# CAN_Cape_v2_1.net
KiCad netlist of a schematic drawn in EAGLE
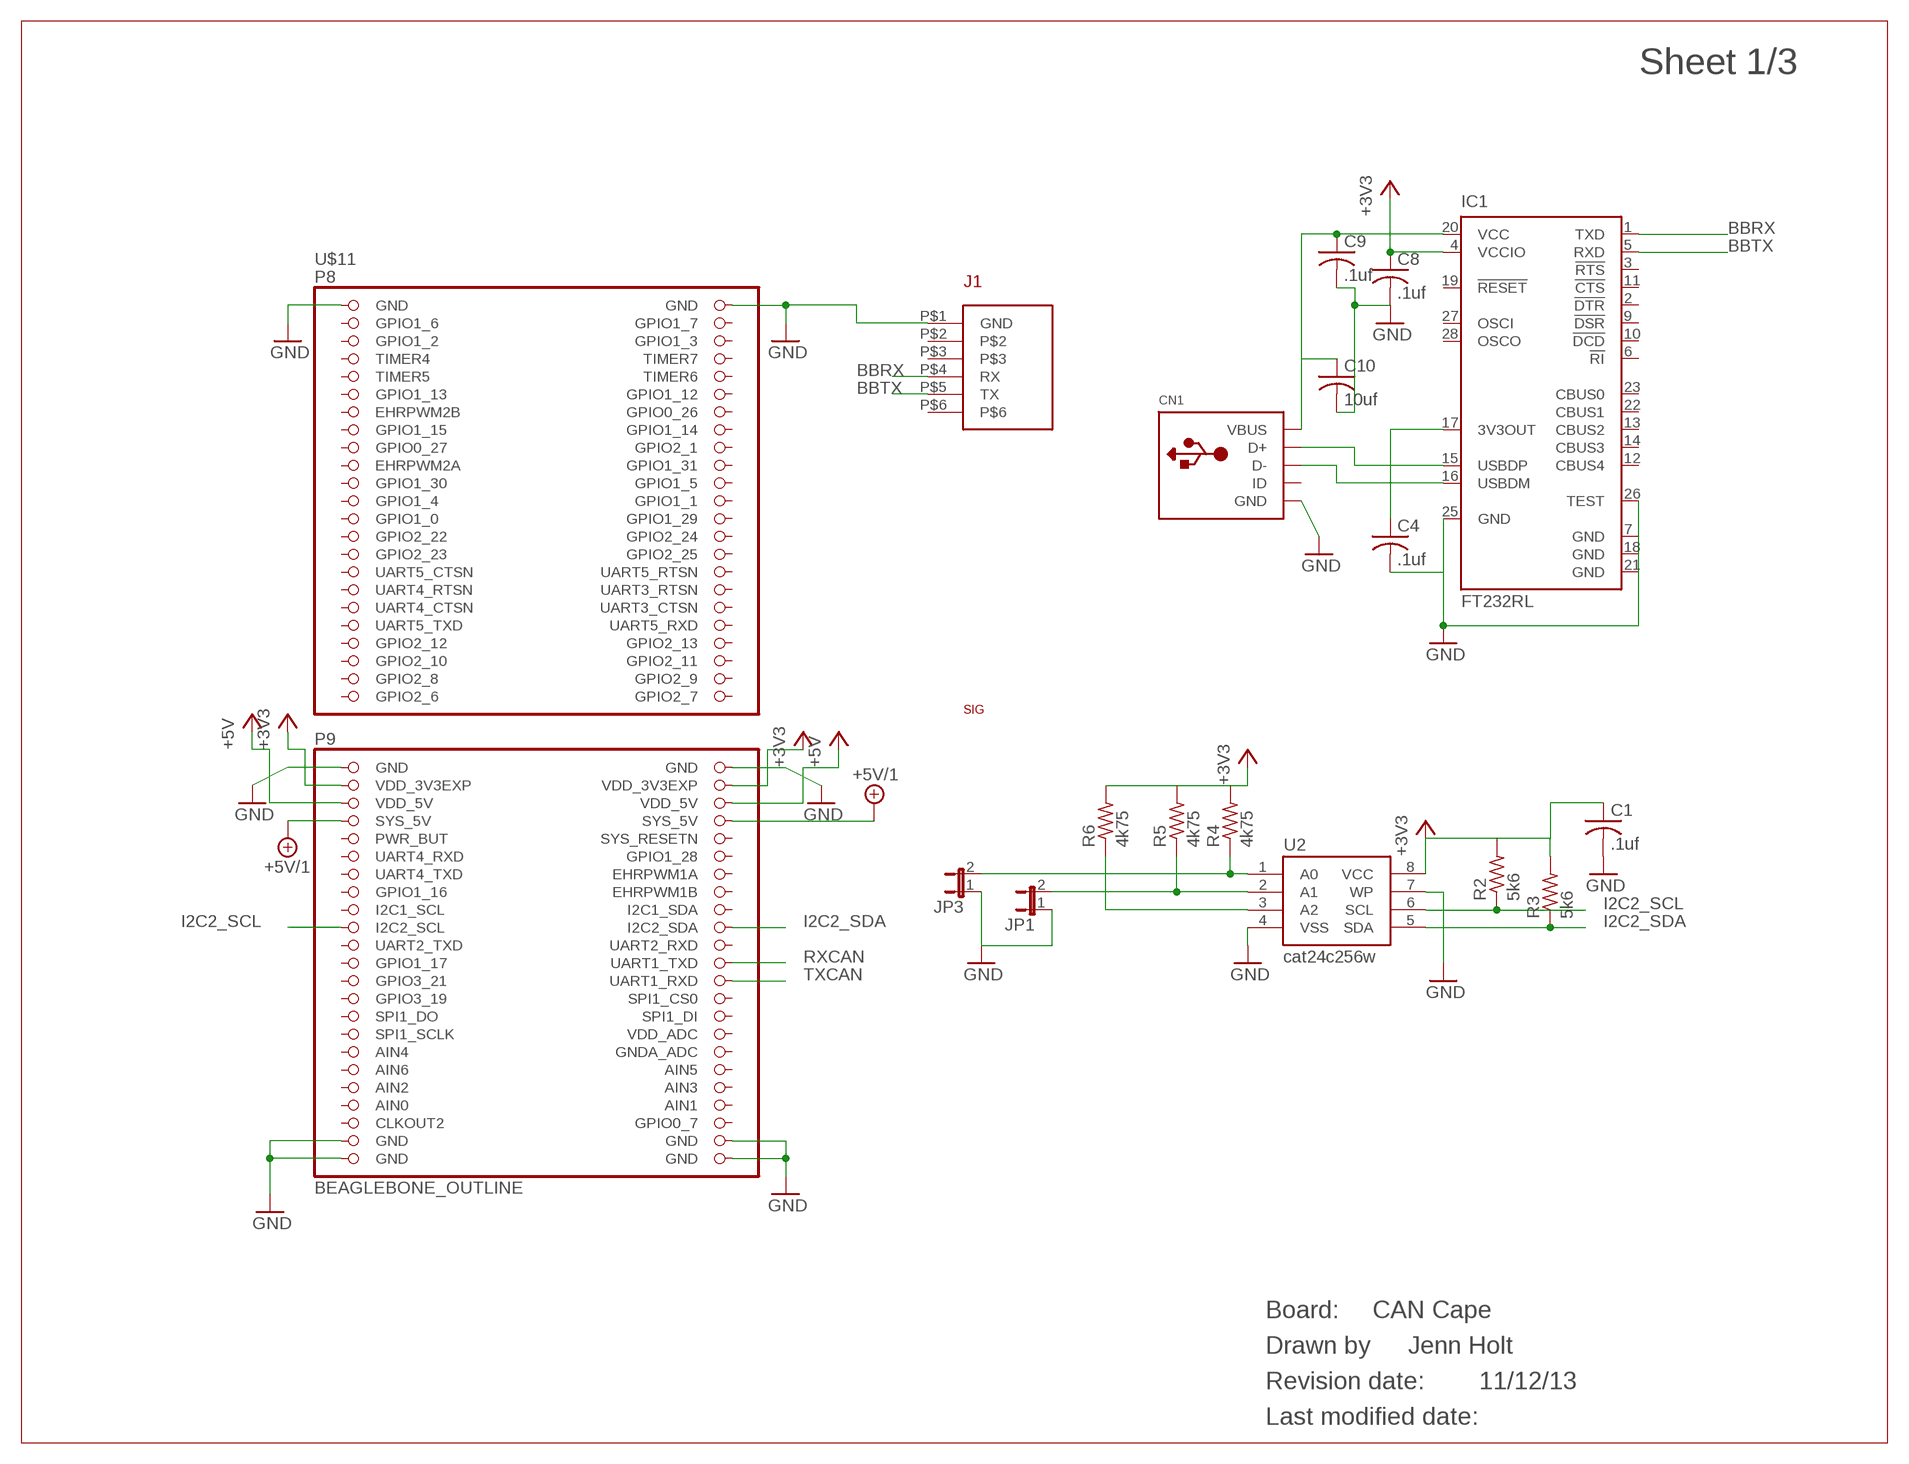
[diagram p0: schematic, sheet 1]
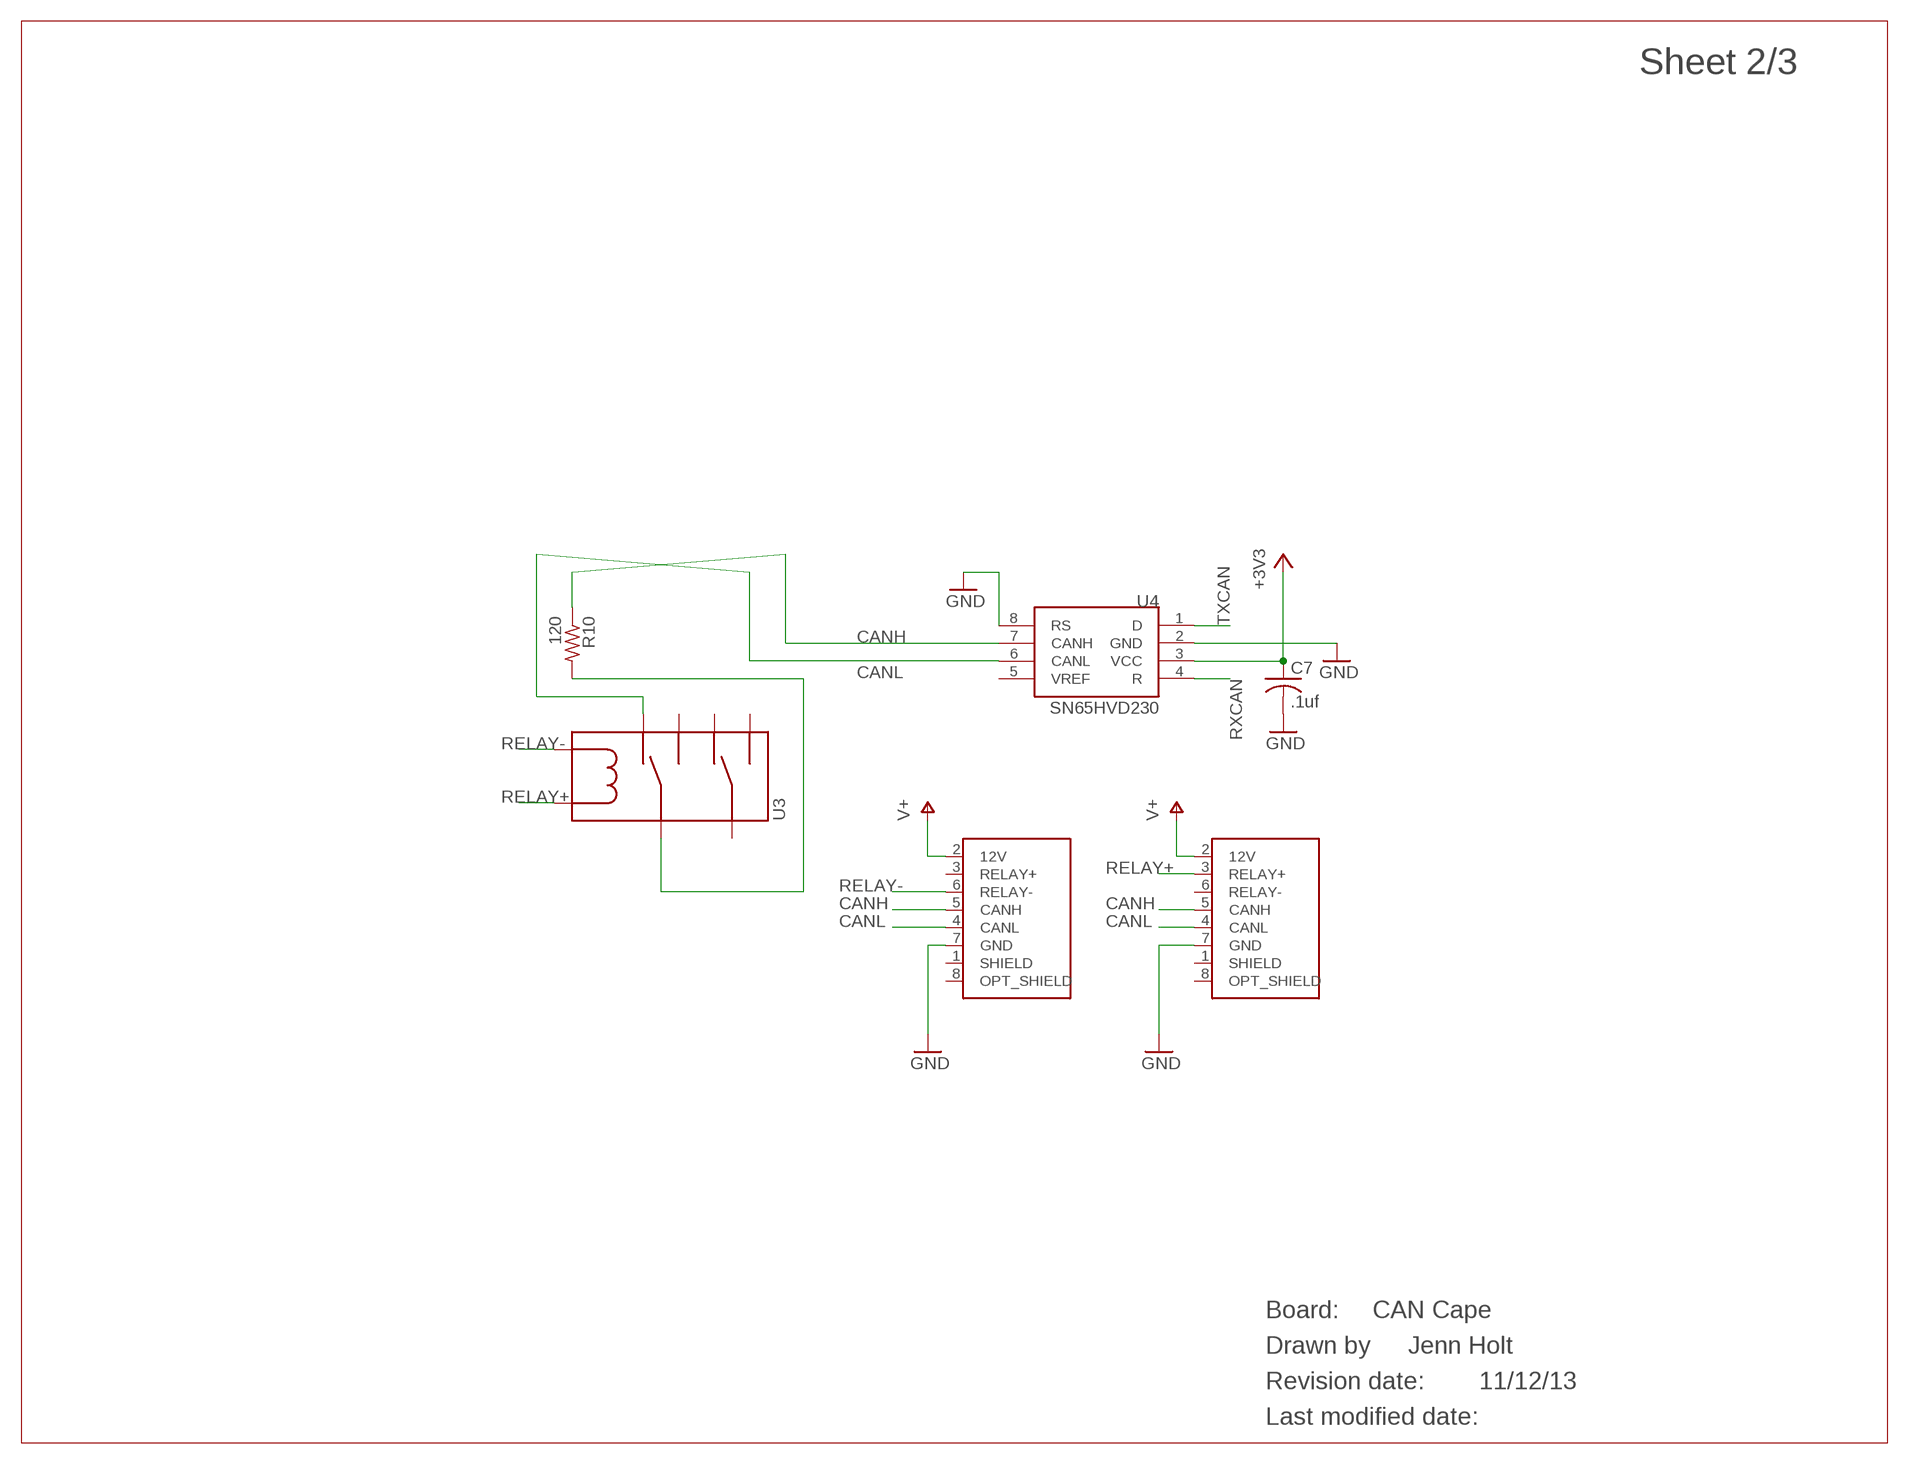
[diagram p1: schematic, sheet 2]
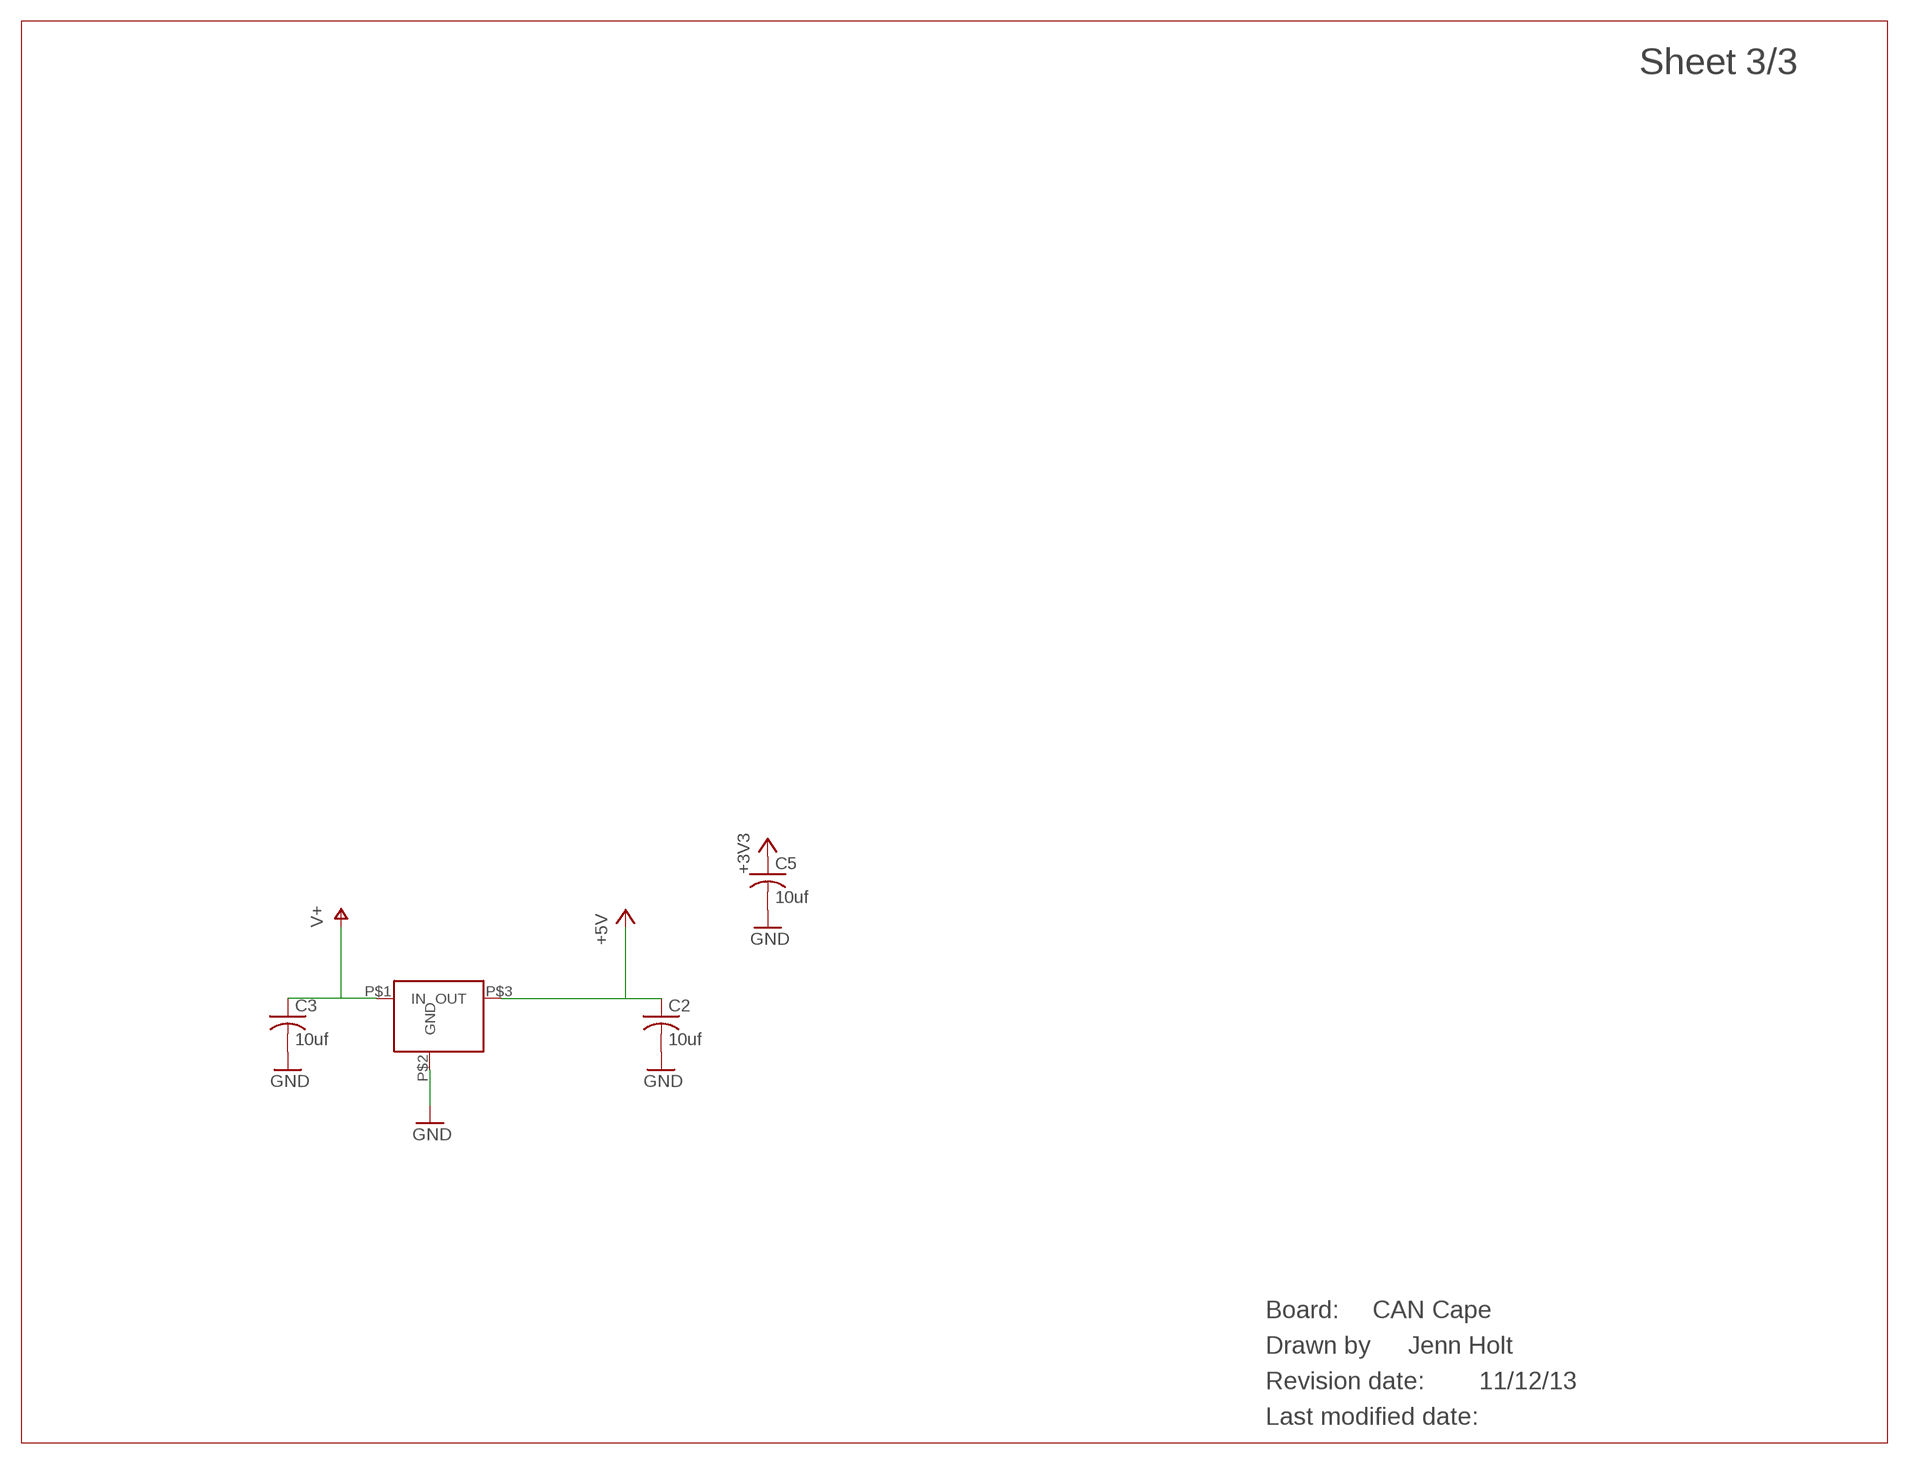
[diagram p2: schematic, sheet 3]

(export (version "E")
  (design (tool "Eeschema 10.0.6"))
  (components
    (comp (ref "C2")
      (value "10uf")
      (footprint "eagle-import:C0805")
      (fields (field (name "PARTNO") "GRM21BR61C106KE15L"))
      (libsource (lib "eagle-import") (part "C-USC0805"))
    )
    (comp (ref "C3")
      (value "10uf")
      (footprint "eagle-import:C0805")
      (fields (field (name "PARTNO") "GRM21BR61C106KE15L"))
      (libsource (lib "eagle-import") (part "C-USC0805"))
    )
    (comp (ref "C5")
      (value "10uf")
      (footprint "eagle-import:C0805")
      (fields (field (name "PARTNO") "GRM21BR61C106KE15L"))
      (libsource (lib "eagle-import") (part "C-USC0805"))
    )
    (comp (ref "U$4")
      (value "CURRENT-C-LETTER-LANDSCAPE")
      (footprint "eagle-import:BLANK")
      (libsource (lib "eagle-import") (part "CURRENT-C-LETTER-LANDSCAPE"))
    )
    (comp (ref "U1")
      (value "RECOM_DCDC")
      (footprint "eagle-import:INNOLINE-SIP")
      (fields (field (name "PARTNO") "R-78C5.0-1.0"))
      (libsource (lib "eagle-import") (part "RECOM_DCDC"))
    )
    (comp (ref "C7")
      (value ".1uf")
      (footprint "eagle-import:C0603")
      (fields (field (name "PARTNO") "C1608X7R1E104K080AA"))
      (libsource (lib "eagle-import") (part "C-USC0603"))
    )
    (comp (ref "R10")
      (value "120")
      (footprint "eagle-import:R0603")
      (fields (field (name "PARTNO") "RC0805FR-07120RL"))
      (libsource (lib "eagle-import") (part "R-US_R0603"))
    )
    (comp (ref "U$6")
      (value "CANBUS2VERT")
      (footprint "eagle-import:776276-1_AMPSEAL_8_VERT")
      (fields (field (name "PARTNO") "1-776276-1"))
      (libsource (lib "eagle-import") (part "CANBUS2VERT"))
    )
    (comp (ref "U$7")
      (value "CANBUS2VERT")
      (footprint "eagle-import:776276-1_AMPSEAL_8_VERT")
      (fields (field (name "PARTNO") "1-776276-1"))
      (libsource (lib "eagle-import") (part "CANBUS2VERT"))
    )
    (comp (ref "U$9")
      (value "CURRENT-C-LETTER-LANDSCAPE")
      (footprint "eagle-import:BLANK")
      (libsource (lib "eagle-import") (part "CURRENT-C-LETTER-LANDSCAPE"))
    )
    (comp (ref "U3")
      (value "IM_RELAY")
      (footprint "eagle-import:IM_RELAY")
      (fields (field (name "PARTNO") "IM26GR"))
      (libsource (lib "eagle-import") (part "IM_RELAY"))
    )
    (comp (ref "U4")
      (value "SN65HVD230")
      (footprint "eagle-import:SOIC8")
      (fields (field (name "PARTNO") "SN65HVD230D"))
      (libsource (lib "eagle-import") (part "SN65HVD230"))
    )
    (comp (ref "C1")
      (value ".1uf")
      (footprint "eagle-import:C0603")
      (fields (field (name "PARTNO") "C1608X7R1E104K080AA"))
      (libsource (lib "eagle-import") (part "C-USC0603"))
    )
    (comp (ref "C4")
      (value ".1uf")
      (footprint "eagle-import:C0603")
      (fields (field (name "PARTNO") "C1608X7R1E104K080AA"))
      (libsource (lib "eagle-import") (part "C-USC0603"))
    )
    (comp (ref "C8")
      (value ".1uf")
      (footprint "eagle-import:C0603")
      (fields (field (name "PARTNO") "C1608X7R1E104K080AA"))
      (libsource (lib "eagle-import") (part "C-USC0603"))
    )
    (comp (ref "C9")
      (value ".1uf")
      (footprint "eagle-import:C0603")
      (fields (field (name "PARTNO") "C1608X7R1E104K080AA"))
      (libsource (lib "eagle-import") (part "C-USC0603"))
    )
    (comp (ref "C10")
      (value "10uf")
      (footprint "eagle-import:C0805")
      (fields (field (name "PARTNO") "GRM21BR61C106KE15L"))
      (libsource (lib "eagle-import") (part "C-USC0805"))
    )
    (comp (ref "CN1")
      (value "USBMINIB")
      (footprint "eagle-import:USB-MINIB")
      (fields (field (name "PARTNO") "1734035-2"))
      (libsource (lib "eagle-import") (part "USBMINIB"))
    )
    (comp (ref "IC1")
      (value "FT232RL")
      (footprint "eagle-import:SSOP28")
      (libsource (lib "eagle-import") (part "FT232RL"))
    )
    (comp (ref "JP1")
      (value "JUMPER-2SMD-NO")
      (footprint "eagle-import:SJ_2S-NO")
      (libsource (lib "eagle-import") (part "JUMPER-2SMD-NO"))
    )
    (comp (ref "JP3")
      (value "JUMPER-2SMD-NO")
      (footprint "eagle-import:SJ_2S-NO")
      (libsource (lib "eagle-import") (part "JUMPER-2SMD-NO"))
    )
    (comp (ref "R2")
      (value "5k6")
      (footprint "eagle-import:R0603")
      (fields (field (name "PARTNO") "ERJ-3EKF4701V"))
      (libsource (lib "eagle-import") (part "R-US_R0603"))
    )
    (comp (ref "R3")
      (value "5k6")
      (footprint "eagle-import:R0603")
      (fields (field (name "PARTNO") "ERJ-3EKF4701V"))
      (libsource (lib "eagle-import") (part "R-US_R0603"))
    )
    (comp (ref "R4")
      (value "4k75")
      (footprint "eagle-import:R0603")
      (fields (field (name "PARTNO") "ERJ-3EKF4701V"))
      (libsource (lib "eagle-import") (part "R-US_R0603"))
    )
    (comp (ref "R5")
      (value "4k75")
      (footprint "eagle-import:R0603")
      (fields (field (name "PARTNO") "ERJ-3EKF4701V"))
      (libsource (lib "eagle-import") (part "R-US_R0603"))
    )
    (comp (ref "R6")
      (value "4k75")
      (footprint "eagle-import:R0603")
      (fields (field (name "PARTNO") "ERJ-3EKF4701V"))
      (libsource (lib "eagle-import") (part "R-US_R0603"))
    )
    (comp (ref "U$5")
      (value "SIG")
      (footprint "eagle-import:SIG")
      (libsource (lib "eagle-import") (part "SIG"))
    )
    (comp (ref "U$10")
      (value "CURRENT-C-LETTER-LANDSCAPE")
      (footprint "eagle-import:BLANK")
      (libsource (lib "eagle-import") (part "CURRENT-C-LETTER-LANDSCAPE"))
    )
    (comp (ref "U$11")
      (value "BEAGLEBONE_OUTLINE")
      (footprint "eagle-import:BEAGLEBONE_SHIELD")
      (libsource (lib "eagle-import") (part "BEAGLEBONE_OUTLINE"))
    )
    (comp (ref "U2")
      (value "cat24c256w")
      (footprint "eagle-import:SO08")
      (fields (field (name "PARTNO") "CAT24C256WI-GT3"))
      (libsource (lib "eagle-import") (part "EEPROM-I2CSMD"))
    )
  )
  (nets
    (net (code "1") (name "+3V3") (class "Default")
      (node (ref "C1") (pin "1") (pinfunction "1_1") (pintype "passive"))
      (node (ref "C5") (pin "1") (pinfunction "1_1") (pintype "passive"))
      (node (ref "C7") (pin "1") (pinfunction "1_1") (pintype "passive"))
      (node (ref "C8") (pin "1") (pinfunction "1_1") (pintype "passive"))
      (node (ref "IC1") (pin "4") (pinfunction "VCCIO_4") (pintype "power_in"))
      (node (ref "R2") (pin "2") (pinfunction "2_2") (pintype "passive"))
      (node (ref "R3") (pin "2") (pinfunction "2_2") (pintype "passive"))
      (node (ref "R4") (pin "2") (pinfunction "2_2") (pintype "passive"))
      (node (ref "R5") (pin "2") (pinfunction "2_2") (pintype "passive"))
      (node (ref "R6") (pin "2") (pinfunction "2_2") (pintype "passive"))
      (node (ref "U$11") (pin "49") (pinfunction "VDD_3V3EXP_49") (pintype "power_in"))
      (node (ref "U$11") (pin "50") (pinfunction "VDD_3V3EXP_50") (pintype "power_in"))
      (node (ref "U2") (pin "8") (pinfunction "VCC_8") (pintype "power_in"))
      (node (ref "U4") (pin "3") (pinfunction "VCC_3") (pintype "bidirectional"))
    )
    (net (code "2") (name "+5V") (class "Default")
      (node (ref "C2") (pin "1") (pinfunction "1_1") (pintype "passive"))
      (node (ref "U$11") (pin "51") (pinfunction "VDD_5V_51") (pintype "power_in"))
      (node (ref "U$11") (pin "52") (pinfunction "VDD_5V_52") (pintype "power_in"))
      (node (ref "U1") (pin "P$3") (pinfunction "OUT_P$3") (pintype "bidirectional"))
    )
    (net (code "3") (name "+5V{slash}1") (class "Default")
      (node (ref "U$11") (pin "53") (pinfunction "SYS_5V_53") (pintype "power_in"))
      (node (ref "U$11") (pin "54") (pinfunction "SYS_5V_54") (pintype "passive"))
    )
    (net (code "4") (name "AIN0") (class "Default")
      (node (ref "U$11") (pin "85") (pinfunction "AIN0_85") (pintype "power_in"))
    )
    (net (code "5") (name "BBRX") (class "Default")
      (node (ref "IC1") (pin "1") (pinfunction "TXD_1") (pintype "output"))
      (node (ref "U$11") (pin "P$4") (pinfunction "RX_P$4") (pintype "bidirectional"))
    )
    (net (code "6") (name "BBTX") (class "Default")
      (node (ref "IC1") (pin "5") (pinfunction "RXD_5") (pintype "input"))
      (node (ref "U$11") (pin "P$5") (pinfunction "TX_P$5") (pintype "bidirectional"))
    )
    (net (code "7") (name "CANH") (class "Default")
      (node (ref "R10") (pin "1") (pinfunction "1_1") (pintype "passive"))
      (node (ref "U$6") (pin "5") (pinfunction "CANH_5") (pintype "bidirectional"))
      (node (ref "U$7") (pin "5") (pinfunction "CANH_5") (pintype "bidirectional"))
      (node (ref "U4") (pin "7") (pinfunction "CANH_7") (pintype "bidirectional"))
    )
    (net (code "8") (name "CANL") (class "Default")
      (node (ref "U$6") (pin "4") (pinfunction "CANL_4") (pintype "bidirectional"))
      (node (ref "U$7") (pin "4") (pinfunction "CANL_4") (pintype "bidirectional"))
      (node (ref "U3") (pin "2") (pinfunction "NC1_2") (pintype "passive"))
      (node (ref "U4") (pin "6") (pinfunction "CANL_6") (pintype "bidirectional"))
    )
    (net (code "9") (name "GND") (class "Default")
      (node (ref "C1") (pin "2") (pinfunction "2_2") (pintype "passive"))
      (node (ref "C10") (pin "2") (pinfunction "2_2") (pintype "passive"))
      (node (ref "C2") (pin "2") (pinfunction "2_2") (pintype "passive"))
      (node (ref "C3") (pin "2") (pinfunction "2_2") (pintype "passive"))
      (node (ref "C4") (pin "2") (pinfunction "2_2") (pintype "passive"))
      (node (ref "C5") (pin "2") (pinfunction "2_2") (pintype "passive"))
      (node (ref "C7") (pin "2") (pinfunction "2_2") (pintype "passive"))
      (node (ref "C8") (pin "2") (pinfunction "2_2") (pintype "passive"))
      (node (ref "C9") (pin "2") (pinfunction "2_2") (pintype "passive"))
      (node (ref "CN1") (pin "GND") (pinfunction "GND_GND") (pintype "power_in"))
      (node (ref "IC1") (pin "18") (pinfunction "GND_18") (pintype "power_in"))
      (node (ref "IC1") (pin "21") (pinfunction "GND_21") (pintype "power_in"))
      (node (ref "IC1") (pin "25") (pinfunction "GND_25") (pintype "power_in"))
      (node (ref "IC1") (pin "26") (pinfunction "TEST_26") (pintype "input"))
      (node (ref "IC1") (pin "7") (pinfunction "GND_7") (pintype "power_in"))
      (node (ref "JP1") (pin "1") (pinfunction "1_1") (pintype "passive"))
      (node (ref "JP3") (pin "1") (pinfunction "1_1") (pintype "passive"))
      (node (ref "U$11") (pin "1") (pinfunction "GND_1") (pintype "power_in"))
      (node (ref "U$11") (pin "2") (pinfunction "GND_2") (pintype "power_in"))
      (node (ref "U$11") (pin "47") (pinfunction "GND_47") (pintype "power_in"))
      (node (ref "U$11") (pin "48") (pinfunction "GND_48") (pintype "power_in"))
      (node (ref "U$11") (pin "89") (pinfunction "GND_89") (pintype "power_in"))
      (node (ref "U$11") (pin "90") (pinfunction "GND_90") (pintype "power_in"))
      (node (ref "U$11") (pin "91") (pinfunction "GND_91") (pintype "power_in"))
      (node (ref "U$11") (pin "92") (pinfunction "GND_92") (pintype "power_in"))
      (node (ref "U$11") (pin "P$1") (pinfunction "GND_P$1") (pintype "bidirectional"))
      (node (ref "U$6") (pin "7") (pinfunction "GND_7") (pintype "bidirectional"))
      (node (ref "U$7") (pin "7") (pinfunction "GND_7") (pintype "bidirectional"))
      (node (ref "U1") (pin "P$2") (pinfunction "GND_P$2") (pintype "bidirectional"))
      (node (ref "U2") (pin "4") (pinfunction "VSS_4") (pintype "power_in"))
      (node (ref "U2") (pin "7") (pinfunction "WP_7") (pintype "bidirectional"))
      (node (ref "U4") (pin "2") (pinfunction "GND_2") (pintype "bidirectional"))
      (node (ref "U4") (pin "8") (pinfunction "RS_8") (pintype "bidirectional"))
    )
    (net (code "10") (name "I2C2_SCL") (class "Default")
      (node (ref "R2") (pin "1") (pinfunction "1_1") (pintype "passive"))
      (node (ref "U$11") (pin "65") (pinfunction "I2C2_SCL_65") (pintype "passive"))
      (node (ref "U2") (pin "6") (pinfunction "SCL_6") (pintype "bidirectional"))
    )
    (net (code "11") (name "I2C2_SDA") (class "Default")
      (node (ref "R3") (pin "1") (pinfunction "1_1") (pintype "passive"))
      (node (ref "U$11") (pin "66") (pinfunction "I2C2_SDA_66") (pintype "passive"))
      (node (ref "U2") (pin "5") (pinfunction "SDA_5") (pintype "bidirectional"))
    )
    (net (code "12") (name "Net-(IC1-3V3OUT)") (class "Default")
      (node (ref "C4") (pin "1") (pinfunction "1_1") (pintype "passive"))
      (node (ref "IC1") (pin "17") (pinfunction "3V3OUT_17") (pintype "output"))
    )
    (net (code "13") (name "Net-(IC1-USBDM)") (class "Default")
      (node (ref "CN1") (pin "D-") (pinfunction "D-_D-") (pintype "bidirectional"))
      (node (ref "IC1") (pin "16") (pinfunction "USBDM_16") (pintype "bidirectional"))
    )
    (net (code "14") (name "Net-(IC1-USBDP)") (class "Default")
      (node (ref "CN1") (pin "D+") (pinfunction "D+_D+") (pintype "bidirectional"))
      (node (ref "IC1") (pin "15") (pinfunction "USBDP_15") (pintype "bidirectional"))
    )
    (net (code "15") (name "Net-(IC1-VCC)") (class "Default")
      (node (ref "C10") (pin "1") (pinfunction "1_1") (pintype "passive"))
      (node (ref "C9") (pin "1") (pinfunction "1_1") (pintype "passive"))
      (node (ref "CN1") (pin "VBUS") (pinfunction "VBUS_VBUS") (pintype "power_in"))
      (node (ref "IC1") (pin "20") (pinfunction "VCC_20") (pintype "power_in"))
    )
    (net (code "16") (name "Net-(U2-A0)") (class "Default")
      (node (ref "JP3") (pin "2") (pinfunction "2_2") (pintype "passive"))
      (node (ref "R4") (pin "1") (pinfunction "1_1") (pintype "passive"))
      (node (ref "U2") (pin "1") (pinfunction "A0_1") (pintype "bidirectional"))
    )
    (net (code "17") (name "Net-(U2-A1)") (class "Default")
      (node (ref "JP1") (pin "2") (pinfunction "2_2") (pintype "passive"))
      (node (ref "R5") (pin "1") (pinfunction "1_1") (pintype "passive"))
      (node (ref "U2") (pin "2") (pinfunction "A1_2") (pintype "bidirectional"))
    )
    (net (code "18") (name "Net-(U2-A2)") (class "Default")
      (node (ref "R6") (pin "1") (pinfunction "1_1") (pintype "passive"))
      (node (ref "U2") (pin "3") (pinfunction "A2_3") (pintype "bidirectional"))
    )
    (net (code "19") (name "Net-(U3-COM1)") (class "Default")
      (node (ref "R10") (pin "2") (pinfunction "2_2") (pintype "passive"))
      (node (ref "U3") (pin "3") (pinfunction "COM1_3") (pintype "passive"))
    )
    (net (code "20") (name "RELAY+") (class "Default")
      (node (ref "U$7") (pin "3") (pinfunction "RELAY+_3") (pintype "bidirectional"))
      (node (ref "U3") (pin "1") (pinfunction "C1_1") (pintype "passive"))
    )
    (net (code "21") (name "RELAY-") (class "Default")
      (node (ref "U$6") (pin "6") (pinfunction "RELAY-_6") (pintype "bidirectional"))
      (node (ref "U3") (pin "8") (pinfunction "C2_8") (pintype "passive"))
    )
    (net (code "22") (name "RXCAN") (class "Default")
      (node (ref "U$11") (pin "70") (pinfunction "UART1_TXD_70") (pintype "passive"))
      (node (ref "U4") (pin "4") (pinfunction "R_4") (pintype "bidirectional"))
    )
    (net (code "23") (name "TXCAN") (class "Default")
      (node (ref "U$11") (pin "72") (pinfunction "UART1_RXD_72") (pintype "passive"))
      (node (ref "U4") (pin "1") (pinfunction "D_1") (pintype "bidirectional"))
    )
    (net (code "24") (name "V+") (class "Default")
      (node (ref "C3") (pin "1") (pinfunction "1_1") (pintype "passive"))
      (node (ref "U$6") (pin "2") (pinfunction "12V_2") (pintype "bidirectional"))
      (node (ref "U$7") (pin "2") (pinfunction "12V_2") (pintype "bidirectional"))
      (node (ref "U1") (pin "P$1") (pinfunction "IN_P$1") (pintype "bidirectional"))
    )
    (net (code "25") (name "unconnected-(CN1-PadID)") (class "Default")
      (node (ref "CN1") (pin "ID") (pinfunction "ID_ID") (pintype "bidirectional"))
    )
    (net (code "26") (name "unconnected-(IC1-CBUS0-Pad23)") (class "Default")
      (node (ref "IC1") (pin "23") (pinfunction "CBUS0_23") (pintype "bidirectional"))
    )
    (net (code "27") (name "unconnected-(IC1-CBUS1-Pad22)") (class "Default")
      (node (ref "IC1") (pin "22") (pinfunction "CBUS1_22") (pintype "bidirectional"))
    )
    (net (code "28") (name "unconnected-(IC1-CBUS2-Pad13)") (class "Default")
      (node (ref "IC1") (pin "13") (pinfunction "CBUS2_13") (pintype "bidirectional"))
    )
    (net (code "29") (name "unconnected-(IC1-CBUS3-Pad14)") (class "Default")
      (node (ref "IC1") (pin "14") (pinfunction "CBUS3_14") (pintype "bidirectional"))
    )
    (net (code "30") (name "unconnected-(IC1-CBUS4-Pad12)") (class "Default")
      (node (ref "IC1") (pin "12") (pinfunction "CBUS4_12") (pintype "bidirectional"))
    )
    (net (code "31") (name "unconnected-(IC1-OSCI-Pad27)") (class "Default")
      (node (ref "IC1") (pin "27") (pinfunction "OSCI_27") (pintype "input"))
    )
    (net (code "32") (name "unconnected-(IC1-OSCO-Pad28)") (class "Default")
      (node (ref "IC1") (pin "28") (pinfunction "OSCO_28") (pintype "output"))
    )
    (net (code "33") (name "unconnected-(IC1-~{CTS}-Pad11)") (class "Default")
      (node (ref "IC1") (pin "11") (pinfunction "~{CTS}_11") (pintype "input"))
    )
    (net (code "34") (name "unconnected-(IC1-~{DCD}-Pad10)") (class "Default")
      (node (ref "IC1") (pin "10") (pinfunction "~{DCD}_10") (pintype "input"))
    )
    (net (code "35") (name "unconnected-(IC1-~{DSR}-Pad9)") (class "Default")
      (node (ref "IC1") (pin "9") (pinfunction "~{DSR}_9") (pintype "input"))
    )
    (net (code "36") (name "unconnected-(IC1-~{DTR}-Pad2)") (class "Default")
      (node (ref "IC1") (pin "2") (pinfunction "~{DTR}_2") (pintype "output"))
    )
    (net (code "37") (name "unconnected-(IC1-~{RESET}-Pad19)") (class "Default")
      (node (ref "IC1") (pin "19") (pinfunction "~{RESET}_19") (pintype "input"))
    )
    (net (code "38") (name "unconnected-(IC1-~{RI}-Pad6)") (class "Default")
      (node (ref "IC1") (pin "6") (pinfunction "~{RI}_6") (pintype "input"))
    )
    (net (code "39") (name "unconnected-(IC1-~{RTS}-Pad3)") (class "Default")
      (node (ref "IC1") (pin "3") (pinfunction "~{RTS}_3") (pintype "output"))
    )
    (net (code "40") (name "unconnected-(U$6-OPT_SHIELD-Pad8)") (class "Default")
      (node (ref "U$6") (pin "8") (pinfunction "OPT_SHIELD_8") (pintype "bidirectional"))
    )
    (net (code "41") (name "unconnected-(U$6-RELAY+-Pad3)") (class "Default")
      (node (ref "U$6") (pin "3") (pinfunction "RELAY+_3") (pintype "bidirectional"))
    )
    (net (code "42") (name "unconnected-(U$6-SHIELD-Pad1)") (class "Default")
      (node (ref "U$6") (pin "1") (pinfunction "SHIELD_1") (pintype "bidirectional"))
    )
    (net (code "43") (name "unconnected-(U$7-OPT_SHIELD-Pad8)") (class "Default")
      (node (ref "U$7") (pin "8") (pinfunction "OPT_SHIELD_8") (pintype "bidirectional"))
    )
    (net (code "44") (name "unconnected-(U$7-RELAY--Pad6)") (class "Default")
      (node (ref "U$7") (pin "6") (pinfunction "RELAY-_6") (pintype "bidirectional"))
    )
    (net (code "45") (name "unconnected-(U$7-SHIELD-Pad1)") (class "Default")
      (node (ref "U$7") (pin "1") (pinfunction "SHIELD_1") (pintype "bidirectional"))
    )
    (net (code "46") (name "unconnected-(U$11-AIN1-Pad86)") (class "Default")
      (node (ref "U$11") (pin "86") (pinfunction "AIN1_86") (pintype "passive"))
    )
    (net (code "47") (name "unconnected-(U$11-AIN2-Pad83)") (class "Default")
      (node (ref "U$11") (pin "83") (pinfunction "AIN2_83") (pintype "passive"))
    )
    (net (code "48") (name "unconnected-(U$11-AIN3-Pad84)") (class "Default")
      (node (ref "U$11") (pin "84") (pinfunction "AIN3_84") (pintype "passive"))
    )
    (net (code "49") (name "unconnected-(U$11-AIN4-Pad79)") (class "Default")
      (node (ref "U$11") (pin "79") (pinfunction "AIN4_79") (pintype "passive"))
    )
    (net (code "50") (name "unconnected-(U$11-AIN5-Pad82)") (class "Default")
      (node (ref "U$11") (pin "82") (pinfunction "AIN5_82") (pintype "passive"))
    )
    (net (code "51") (name "unconnected-(U$11-AIN6-Pad81)") (class "Default")
      (node (ref "U$11") (pin "81") (pinfunction "AIN6_81") (pintype "passive"))
    )
    (net (code "52") (name "unconnected-(U$11-CLKOUT2-Pad87)") (class "Default")
      (node (ref "U$11") (pin "87") (pinfunction "CLKOUT2_87") (pintype "input"))
    )
    (net (code "53") (name "unconnected-(U$11-EHRPWM1A-Pad60)") (class "Default")
      (node (ref "U$11") (pin "60") (pinfunction "EHRPWM1A_60") (pintype "passive"))
    )
    (net (code "54") (name "unconnected-(U$11-EHRPWM1B-Pad62)") (class "Default")
      (node (ref "U$11") (pin "62") (pinfunction "EHRPWM1B_62") (pintype "passive"))
    )
    (net (code "55") (name "unconnected-(U$11-EHRPWM2A-Pad19)") (class "Default")
      (node (ref "U$11") (pin "19") (pinfunction "EHRPWM2A_19") (pintype "passive"))
    )
    (net (code "56") (name "unconnected-(U$11-EHRPWM2B-Pad13)") (class "Default")
      (node (ref "U$11") (pin "13") (pinfunction "EHRPWM2B_13") (pintype "passive"))
    )
    (net (code "57") (name "unconnected-(U$11-GNDA_ADC-Pad80)") (class "Default")
      (node (ref "U$11") (pin "80") (pinfunction "GNDA_ADC_80") (pintype "passive"))
    )
    (net (code "58") (name "unconnected-(U$11-GPIO0_7-Pad88)") (class "Default")
      (node (ref "U$11") (pin "88") (pinfunction "GPIO0_7_88") (pintype "passive"))
    )
    (net (code "59") (name "unconnected-(U$11-GPIO0_26-Pad14)") (class "Default")
      (node (ref "U$11") (pin "14") (pinfunction "GPIO0_26_14") (pintype "passive"))
    )
    (net (code "60") (name "unconnected-(U$11-GPIO0_27-Pad17)") (class "Default")
      (node (ref "U$11") (pin "17") (pinfunction "GPIO0_27_17") (pintype "passive"))
    )
    (net (code "61") (name "unconnected-(U$11-GPIO1_0-Pad25)") (class "Default")
      (node (ref "U$11") (pin "25") (pinfunction "GPIO1_0_25") (pintype "passive"))
    )
    (net (code "62") (name "unconnected-(U$11-GPIO1_1-Pad24)") (class "Default")
      (node (ref "U$11") (pin "24") (pinfunction "GPIO1_1_24") (pintype "passive"))
    )
    (net (code "63") (name "unconnected-(U$11-GPIO1_2-Pad5)") (class "Default")
      (node (ref "U$11") (pin "5") (pinfunction "GPIO1_2_5") (pintype "passive"))
    )
    (net (code "64") (name "unconnected-(U$11-GPIO1_3-Pad6)") (class "Default")
      (node (ref "U$11") (pin "6") (pinfunction "GPIO1_3_6") (pintype "passive"))
    )
    (net (code "65") (name "unconnected-(U$11-GPIO1_4-Pad23)") (class "Default")
      (node (ref "U$11") (pin "23") (pinfunction "GPIO1_4_23") (pintype "passive"))
    )
    (net (code "66") (name "unconnected-(U$11-GPIO1_5-Pad22)") (class "Default")
      (node (ref "U$11") (pin "22") (pinfunction "GPIO1_5_22") (pintype "passive"))
    )
    (net (code "67") (name "unconnected-(U$11-GPIO1_6-Pad3)") (class "Default")
      (node (ref "U$11") (pin "3") (pinfunction "GPIO1_6_3") (pintype "passive"))
    )
    (net (code "68") (name "unconnected-(U$11-GPIO1_7-Pad4)") (class "Default")
      (node (ref "U$11") (pin "4") (pinfunction "GPIO1_7_4") (pintype "passive"))
    )
    (net (code "69") (name "unconnected-(U$11-GPIO1_12-Pad12)") (class "Default")
      (node (ref "U$11") (pin "12") (pinfunction "GPIO1_12_12") (pintype "passive"))
    )
    (net (code "70") (name "unconnected-(U$11-GPIO1_13-Pad11)") (class "Default")
      (node (ref "U$11") (pin "11") (pinfunction "GPIO1_13_11") (pintype "passive"))
    )
    (net (code "71") (name "unconnected-(U$11-GPIO1_14-Pad16)") (class "Default")
      (node (ref "U$11") (pin "16") (pinfunction "GPIO1_14_16") (pintype "passive"))
    )
    (net (code "72") (name "unconnected-(U$11-GPIO1_15-Pad15)") (class "Default")
      (node (ref "U$11") (pin "15") (pinfunction "GPIO1_15_15") (pintype "passive"))
    )
    (net (code "73") (name "unconnected-(U$11-GPIO1_16-Pad61)") (class "Default")
      (node (ref "U$11") (pin "61") (pinfunction "GPIO1_16_61") (pintype "passive"))
    )
    (net (code "74") (name "unconnected-(U$11-GPIO1_17-Pad69)") (class "Default")
      (node (ref "U$11") (pin "69") (pinfunction "GPIO1_17_69") (pintype "passive"))
    )
    (net (code "75") (name "unconnected-(U$11-GPIO1_28-Pad58)") (class "Default")
      (node (ref "U$11") (pin "58") (pinfunction "GPIO1_28_58") (pintype "passive"))
    )
    (net (code "76") (name "unconnected-(U$11-GPIO1_29-Pad26)") (class "Default")
      (node (ref "U$11") (pin "26") (pinfunction "GPIO1_29_26") (pintype "passive"))
    )
    (net (code "77") (name "unconnected-(U$11-GPIO1_30-Pad21)") (class "Default")
      (node (ref "U$11") (pin "21") (pinfunction "GPIO1_30_21") (pintype "passive"))
    )
    (net (code "78") (name "unconnected-(U$11-GPIO1_31-Pad20)") (class "Default")
      (node (ref "U$11") (pin "20") (pinfunction "GPIO1_31_20") (pintype "passive"))
    )
    (net (code "79") (name "unconnected-(U$11-GPIO2_1-Pad18)") (class "Default")
      (node (ref "U$11") (pin "18") (pinfunction "GPIO2_1_18") (pintype "passive"))
    )
    (net (code "80") (name "unconnected-(U$11-GPIO2_6-Pad45)") (class "Default")
      (node (ref "U$11") (pin "45") (pinfunction "GPIO2_6_45") (pintype "passive"))
    )
    (net (code "81") (name "unconnected-(U$11-GPIO2_7-Pad46)") (class "Default")
      (node (ref "U$11") (pin "46") (pinfunction "GPIO2_7_46") (pintype "passive"))
    )
    (net (code "82") (name "unconnected-(U$11-GPIO2_8-Pad43)") (class "Default")
      (node (ref "U$11") (pin "43") (pinfunction "GPIO2_8_43") (pintype "passive"))
    )
    (net (code "83") (name "unconnected-(U$11-GPIO2_9-Pad44)") (class "Default")
      (node (ref "U$11") (pin "44") (pinfunction "GPIO2_9_44") (pintype "passive"))
    )
    (net (code "84") (name "unconnected-(U$11-GPIO2_10-Pad41)") (class "Default")
      (node (ref "U$11") (pin "41") (pinfunction "GPIO2_10_41") (pintype "passive"))
    )
    (net (code "85") (name "unconnected-(U$11-GPIO2_11-Pad42)") (class "Default")
      (node (ref "U$11") (pin "42") (pinfunction "GPIO2_11_42") (pintype "passive"))
    )
    (net (code "86") (name "unconnected-(U$11-GPIO2_12-Pad39)") (class "Default")
      (node (ref "U$11") (pin "39") (pinfunction "GPIO2_12_39") (pintype "passive"))
    )
    (net (code "87") (name "unconnected-(U$11-GPIO2_13-Pad40)") (class "Default")
      (node (ref "U$11") (pin "40") (pinfunction "GPIO2_13_40") (pintype "passive"))
    )
    (net (code "88") (name "unconnected-(U$11-GPIO2_22-Pad27)") (class "Default")
      (node (ref "U$11") (pin "27") (pinfunction "GPIO2_22_27") (pintype "passive"))
    )
    (net (code "89") (name "unconnected-(U$11-GPIO2_23-Pad29)") (class "Default")
      (node (ref "U$11") (pin "29") (pinfunction "GPIO2_23_29") (pintype "passive"))
    )
    (net (code "90") (name "unconnected-(U$11-GPIO2_24-Pad28)") (class "Default")
      (node (ref "U$11") (pin "28") (pinfunction "GPIO2_24_28") (pintype "passive"))
    )
    (net (code "91") (name "unconnected-(U$11-GPIO2_25-Pad30)") (class "Default")
      (node (ref "U$11") (pin "30") (pinfunction "GPIO2_25_30") (pintype "passive"))
    )
    (net (code "92") (name "unconnected-(U$11-GPIO3_19-Pad73)") (class "Default")
      (node (ref "U$11") (pin "73") (pinfunction "GPIO3_19_73") (pintype "passive"))
    )
    (net (code "93") (name "unconnected-(U$11-GPIO3_21-Pad71)") (class "Default")
      (node (ref "U$11") (pin "71") (pinfunction "GPIO3_21_71") (pintype "passive"))
    )
    (net (code "94") (name "unconnected-(U$11-I2C1_SCL-Pad63)") (class "Default")
      (node (ref "U$11") (pin "63") (pinfunction "I2C1_SCL_63") (pintype "passive"))
    )
    (net (code "95") (name "unconnected-(U$11-I2C1_SDA-Pad64)") (class "Default")
      (node (ref "U$11") (pin "64") (pinfunction "I2C1_SDA_64") (pintype "passive"))
    )
    (net (code "96") (name "unconnected-(U$11-PWR_BUT-Pad55)") (class "Default")
      (node (ref "U$11") (pin "55") (pinfunction "PWR_BUT_55") (pintype "passive"))
    )
    (net (code "97") (name "unconnected-(U$11-PadP$2)") (class "Default")
      (node (ref "U$11") (pin "P$2") (pinfunction "P$2_P$2") (pintype "bidirectional"))
    )
    (net (code "98") (name "unconnected-(U$11-PadP$3)") (class "Default")
      (node (ref "U$11") (pin "P$3") (pinfunction "P$3_P$3") (pintype "bidirectional"))
    )
    (net (code "99") (name "unconnected-(U$11-PadP$6)") (class "Default")
      (node (ref "U$11") (pin "P$6") (pinfunction "P$6_P$6") (pintype "bidirectional"))
    )
    (net (code "100") (name "unconnected-(U$11-SPI1_CS0-Pad74)") (class "Default")
      (node (ref "U$11") (pin "74") (pinfunction "SPI1_CS0_74") (pintype "passive"))
    )
    (net (code "101") (name "unconnected-(U$11-SPI1_DI-Pad76)") (class "Default")
      (node (ref "U$11") (pin "76") (pinfunction "SPI1_DI_76") (pintype "passive"))
    )
    (net (code "102") (name "unconnected-(U$11-SPI1_DO-Pad75)") (class "Default")
      (node (ref "U$11") (pin "75") (pinfunction "SPI1_DO_75") (pintype "passive"))
    )
    (net (code "103") (name "unconnected-(U$11-SPI1_SCLK-Pad77)") (class "Default")
      (node (ref "U$11") (pin "77") (pinfunction "SPI1_SCLK_77") (pintype "passive"))
    )
    (net (code "104") (name "unconnected-(U$11-SYS_RESETN-Pad56)") (class "Default")
      (node (ref "U$11") (pin "56") (pinfunction "SYS_RESETN_56") (pintype "passive"))
    )
    (net (code "105") (name "unconnected-(U$11-TIMER4-Pad7)") (class "Default")
      (node (ref "U$11") (pin "7") (pinfunction "TIMER4_7") (pintype "passive"))
    )
    (net (code "106") (name "unconnected-(U$11-TIMER5-Pad9)") (class "Default")
      (node (ref "U$11") (pin "9") (pinfunction "TIMER5_9") (pintype "passive"))
    )
    (net (code "107") (name "unconnected-(U$11-TIMER6-Pad10)") (class "Default")
      (node (ref "U$11") (pin "10") (pinfunction "TIMER6_10") (pintype "passive"))
    )
    (net (code "108") (name "unconnected-(U$11-TIMER7-Pad8)") (class "Default")
      (node (ref "U$11") (pin "8") (pinfunction "TIMER7_8") (pintype "passive"))
    )
    (net (code "109") (name "unconnected-(U$11-UART2_RXD-Pad68)") (class "Default")
      (node (ref "U$11") (pin "68") (pinfunction "UART2_RXD_68") (pintype "passive"))
    )
    (net (code "110") (name "unconnected-(U$11-UART2_TXD-Pad67)") (class "Default")
      (node (ref "U$11") (pin "67") (pinfunction "UART2_TXD_67") (pintype "passive"))
    )
    (net (code "111") (name "unconnected-(U$11-UART3_CTSN-Pad36)") (class "Default")
      (node (ref "U$11") (pin "36") (pinfunction "UART3_CTSN_36") (pintype "passive"))
    )
    (net (code "112") (name "unconnected-(U$11-UART3_RTSN-Pad34)") (class "Default")
      (node (ref "U$11") (pin "34") (pinfunction "UART3_RTSN_34") (pintype "passive"))
    )
    (net (code "113") (name "unconnected-(U$11-UART4_CTSN-Pad35)") (class "Default")
      (node (ref "U$11") (pin "35") (pinfunction "UART4_CTSN_35") (pintype "passive"))
    )
    (net (code "114") (name "unconnected-(U$11-UART4_RTSN-Pad33)") (class "Default")
      (node (ref "U$11") (pin "33") (pinfunction "UART4_RTSN_33") (pintype "passive"))
    )
    (net (code "115") (name "unconnected-(U$11-UART4_RXD-Pad57)") (class "Default")
      (node (ref "U$11") (pin "57") (pinfunction "UART4_RXD_57") (pintype "passive"))
    )
    (net (code "116") (name "unconnected-(U$11-UART4_TXD-Pad59)") (class "Default")
      (node (ref "U$11") (pin "59") (pinfunction "UART4_TXD_59") (pintype "passive"))
    )
    (net (code "117") (name "unconnected-(U$11-UART5_CTSN-Pad31)") (class "Default")
      (node (ref "U$11") (pin "31") (pinfunction "UART5_CTSN_31") (pintype "passive"))
    )
    (net (code "118") (name "unconnected-(U$11-UART5_RTSN-Pad32)") (class "Default")
      (node (ref "U$11") (pin "32") (pinfunction "UART5_RTSN_32") (pintype "passive"))
    )
    (net (code "119") (name "unconnected-(U$11-UART5_RXD-Pad38)") (class "Default")
      (node (ref "U$11") (pin "38") (pinfunction "UART5_RXD_38") (pintype "passive"))
    )
    (net (code "120") (name "unconnected-(U$11-UART5_TXD-Pad37)") (class "Default")
      (node (ref "U$11") (pin "37") (pinfunction "UART5_TXD_37") (pintype "passive"))
    )
    (net (code "121") (name "unconnected-(U$11-VDD_ADC-Pad78)") (class "Default")
      (node (ref "U$11") (pin "78") (pinfunction "VDD_ADC_78") (pintype "passive"))
    )
    (net (code "122") (name "unconnected-(U3-COM2-Pad6)") (class "Default")
      (node (ref "U3") (pin "6") (pinfunction "COM2_6") (pintype "passive"))
    )
    (net (code "123") (name "unconnected-(U3-NC2-Pad7)") (class "Default")
      (node (ref "U3") (pin "7") (pinfunction "NC2_7") (pintype "passive"))
    )
    (net (code "124") (name "unconnected-(U3-NO1-Pad4)") (class "Default")
      (node (ref "U3") (pin "4") (pinfunction "NO1_4") (pintype "passive"))
    )
    (net (code "125") (name "unconnected-(U3-NO2-Pad5)") (class "Default")
      (node (ref "U3") (pin "5") (pinfunction "NO2_5") (pintype "passive"))
    )
    (net (code "126") (name "unconnected-(U4-VREF-Pad5)") (class "Default")
      (node (ref "U4") (pin "5") (pinfunction "VREF_5") (pintype "bidirectional"))
    )
  )
)
